# 11_Speak.net
KiCad netlist of a schematic drawn in Altium Designer
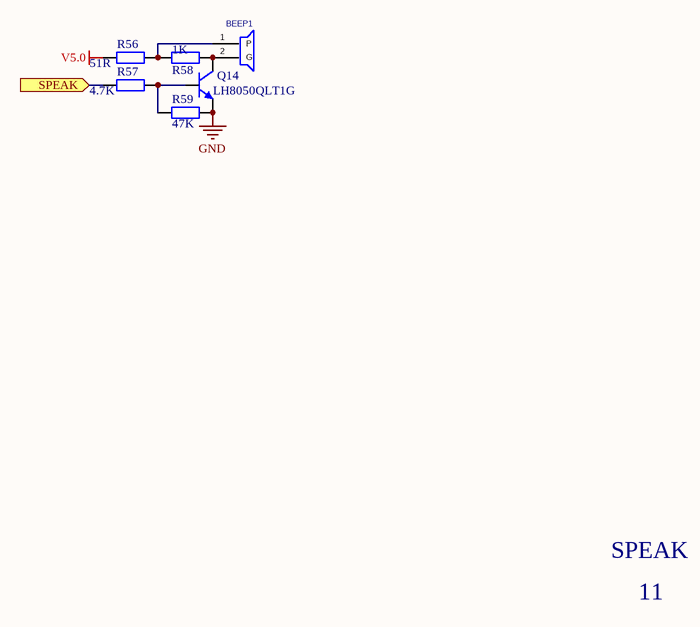
[diagram p0: 11_Speak.SchDoc]

(export (version "E")
  (design (tool "Eeschema 10.0.6"))
  (components
    (comp (ref "BEEP1")
      (value "BEEP-9.5X5.5")
      (footprint "BEEP-9.5X5.5")
      (libsource (lib "MINI-V3") (part "BEEP-9.5X5.5"))
    )
    (comp (ref "Q14")
      (value "LH8050QLT1G")
      (footprint "SOT-23")
      (description "NPN")
      (libsource (lib "XiaoyI") (part "NPN-1"))
    )
    (comp (ref "R56")
      (value "51R")
      (footprint "SMD-0603")
      (description "贴片电阻 5%")
      (libsource (lib "ABB") (part "RES0"))
    )
    (comp (ref "R57")
      (value "4.7K")
      (footprint "SMD-0603")
      (description "贴片电阻 5%")
      (libsource (lib "") (part "RES0_1"))
    )
    (comp (ref "R58")
      (value "1K")
      (footprint "SMD-0603")
      (description "贴片电阻 5%")
      (libsource (lib "ABB") (part "RES0"))
    )
    (comp (ref "R59")
      (value "47K")
      (footprint "SMD-0603")
      (description "贴片电阻 5%")
      (libsource (lib "") (part "RES0_1"))
    )
  )
  (nets
    (net (code "1") (name "/SPEAK") (class "Default")
      (node (ref "R57") (pin "1") (pinfunction "1_1") (pintype "passive"))
    )
    (net (code "2") (name "GND") (class "Default")
      (node (ref "Q14") (pin "2") (pinfunction "E_2") (pintype "passive"))
      (node (ref "R59") (pin "2") (pinfunction "2_2") (pintype "passive"))
    )
    (net (code "3") (name "Net-(BEEP1-G)") (class "Default")
      (node (ref "BEEP1") (pin "2") (pinfunction "G_2") (pintype "passive"))
      (node (ref "Q14") (pin "3") (pinfunction "C_3") (pintype "passive"))
      (node (ref "R58") (pin "1") (pinfunction "1_1") (pintype "passive"))
    )
    (net (code "4") (name "Net-(BEEP1-P)") (class "Default")
      (node (ref "BEEP1") (pin "1") (pinfunction "P_1") (pintype "passive"))
      (node (ref "R56") (pin "1") (pinfunction "1_1") (pintype "passive"))
      (node (ref "R58") (pin "2") (pinfunction "2_2") (pintype "passive"))
    )
    (net (code "5") (name "Net-(Q14-B)") (class "Default")
      (node (ref "Q14") (pin "1") (pinfunction "B_1") (pintype "passive"))
      (node (ref "R57") (pin "2") (pinfunction "2_2") (pintype "passive"))
      (node (ref "R59") (pin "1") (pinfunction "1_1") (pintype "passive"))
    )
    (net (code "6") (name "V5.0") (class "Default")
      (node (ref "R56") (pin "2") (pinfunction "2_2") (pintype "passive"))
    )
  )
)
